# stepperDriverTop.net
KiCad netlist of a schematic drawn in EAGLE
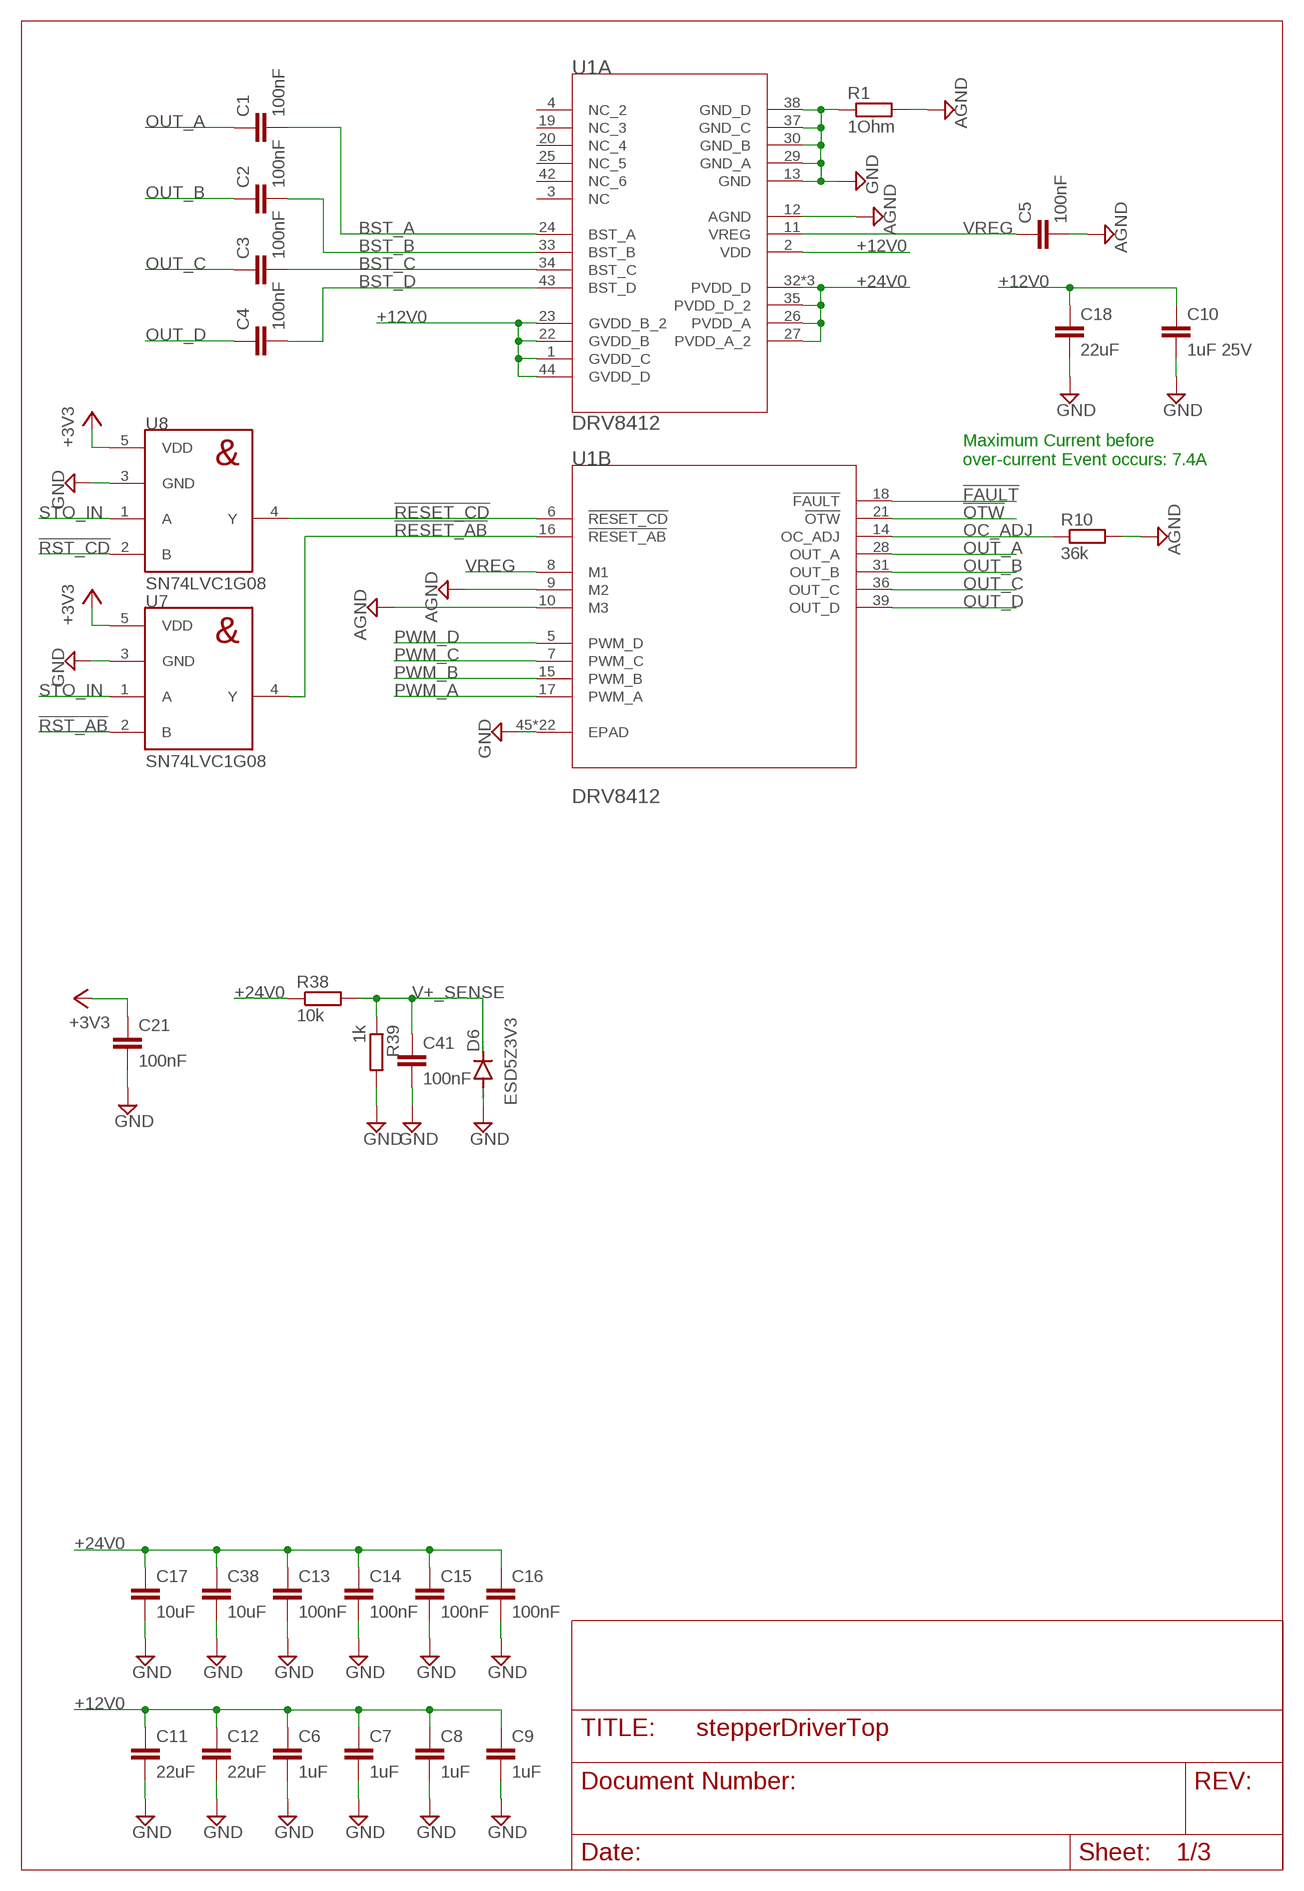
[diagram p0: schematic, sheet 1]
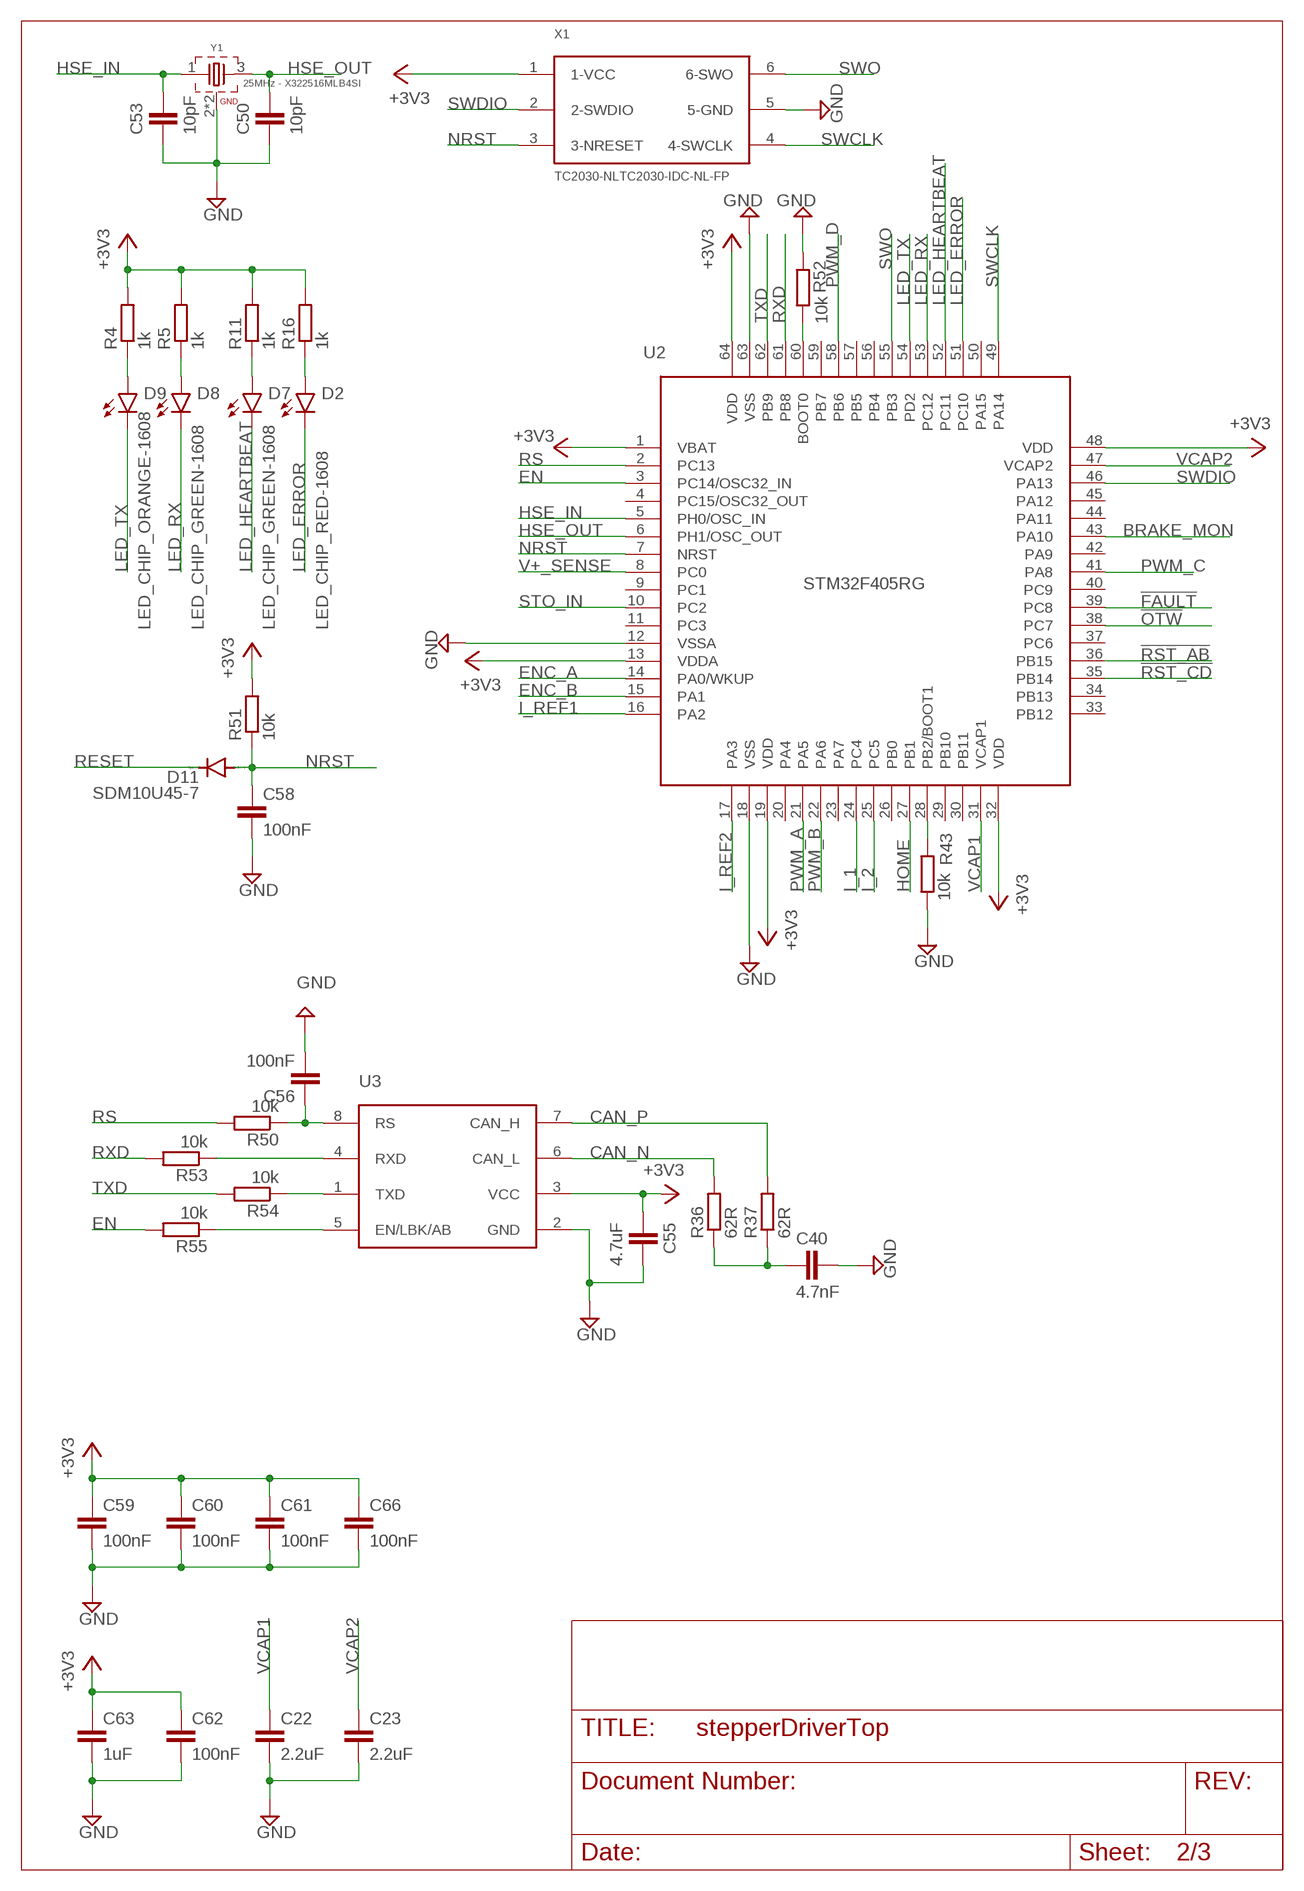
[diagram p1: schematic, sheet 2]
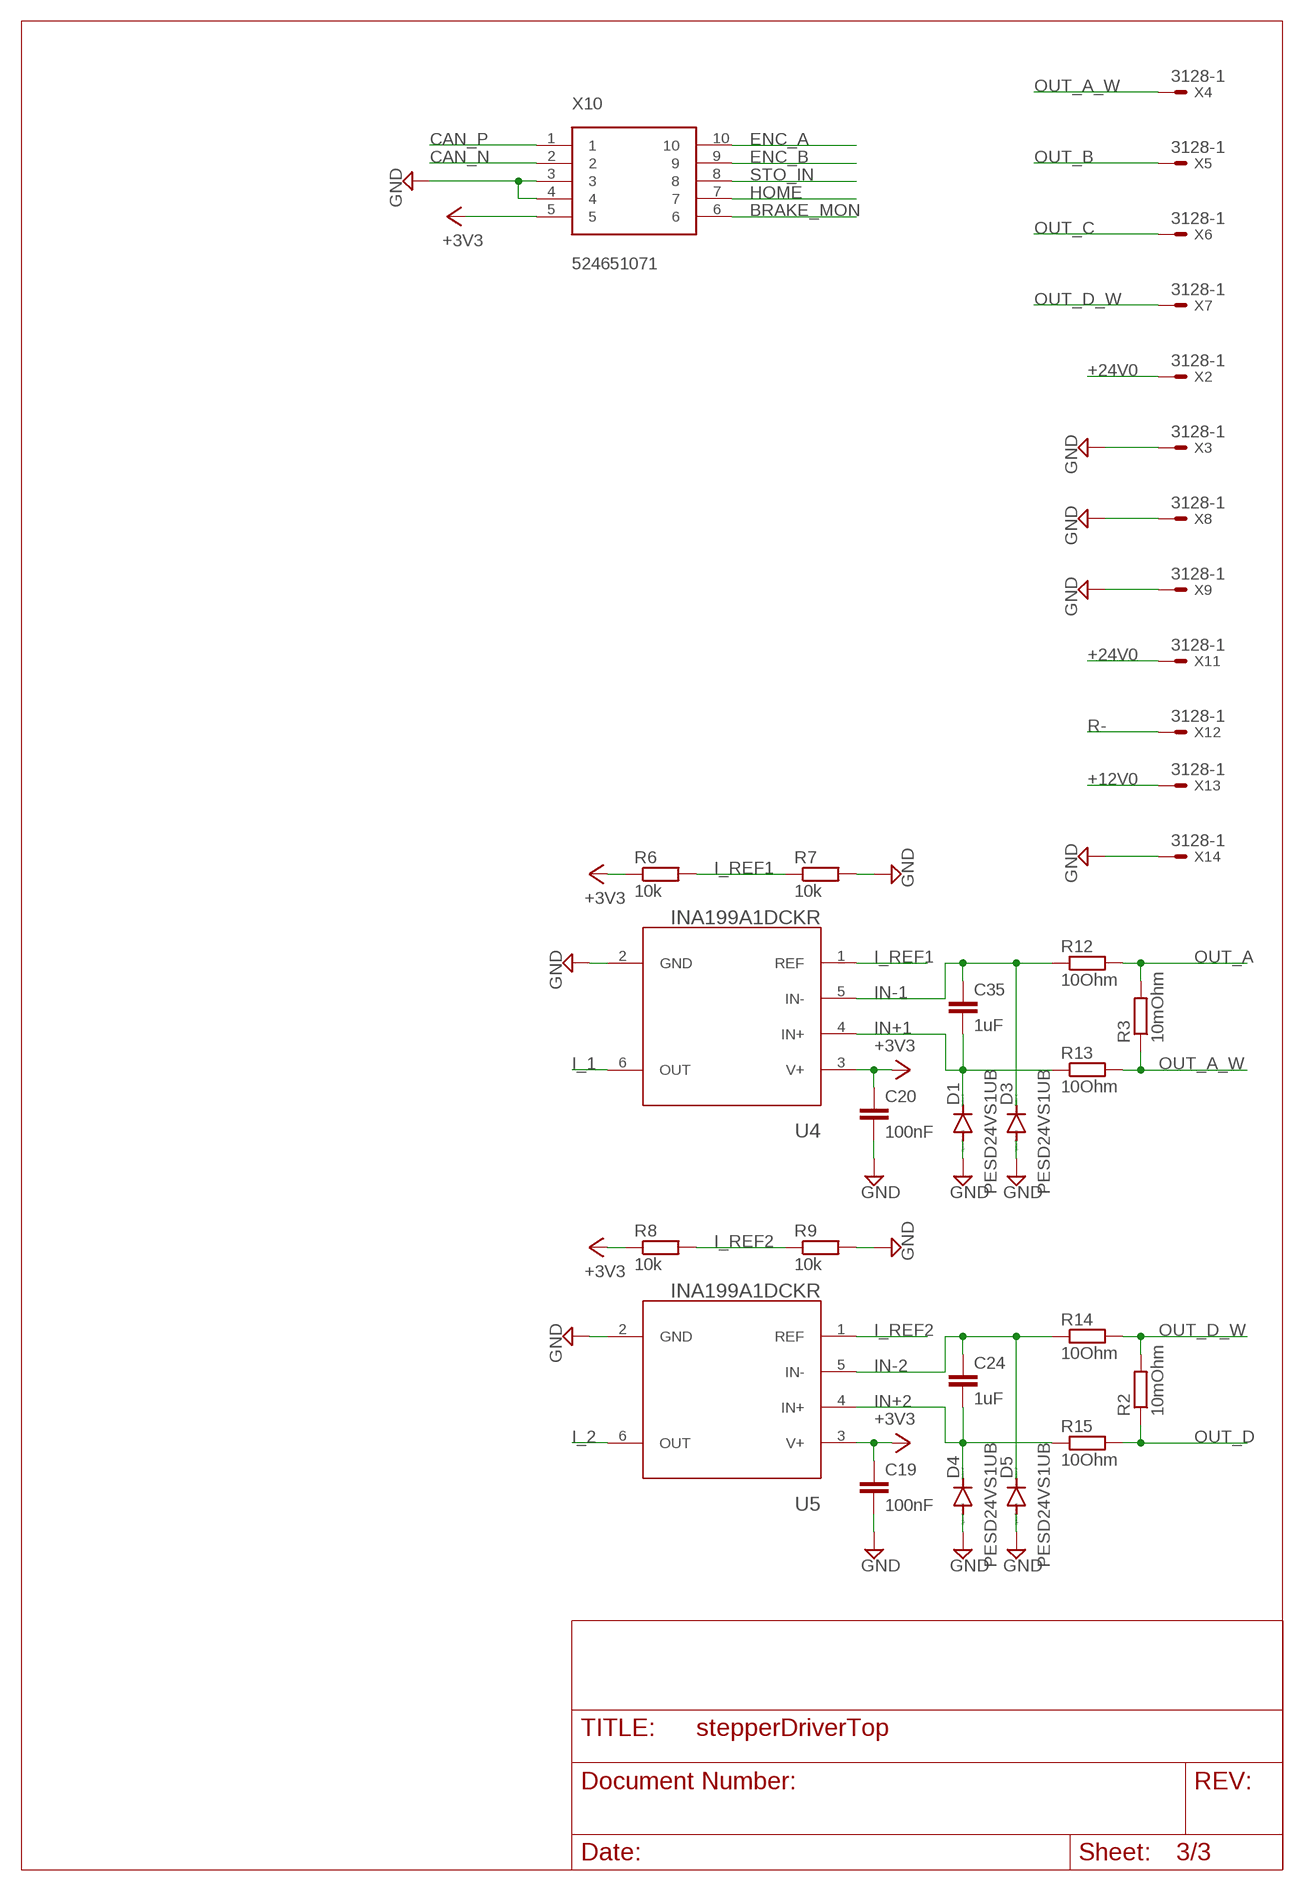
[diagram p2: schematic, sheet 3]

(export (version "E")
  (design (tool "Eeschema 10.0.6"))
  (components
    (comp (ref "C1")
      (value "100nF")
      (footprint "eagle-import:C0603")
      (libsource (lib "eagle-import") (part "C-EUC0603"))
    )
    (comp (ref "C2")
      (value "100nF")
      (footprint "eagle-import:C0603")
      (libsource (lib "eagle-import") (part "C-EUC0603"))
    )
    (comp (ref "C3")
      (value "100nF")
      (footprint "eagle-import:C0603")
      (libsource (lib "eagle-import") (part "C-EUC0603"))
    )
    (comp (ref "C4")
      (value "100nF")
      (footprint "eagle-import:C0603")
      (libsource (lib "eagle-import") (part "C-EUC0603"))
    )
    (comp (ref "C5")
      (value "100nF")
      (footprint "eagle-import:C0402")
      (libsource (lib "eagle-import") (part "C-EUC0402"))
    )
    (comp (ref "C6")
      (value "1uF")
      (footprint "eagle-import:C0402")
      (libsource (lib "eagle-import") (part "C-EUC0402"))
    )
    (comp (ref "C7")
      (value "1uF")
      (footprint "eagle-import:C0402")
      (libsource (lib "eagle-import") (part "C-EUC0402"))
    )
    (comp (ref "C8")
      (value "1uF")
      (footprint "eagle-import:C0402")
      (libsource (lib "eagle-import") (part "C-EUC0402"))
    )
    (comp (ref "C9")
      (value "1uF")
      (footprint "eagle-import:C0402")
      (libsource (lib "eagle-import") (part "C-EUC0402"))
    )
    (comp (ref "C10")
      (value "1uF 25V")
      (footprint "eagle-import:C0402")
      (libsource (lib "eagle-import") (part "C-EUC0402"))
    )
    (comp (ref "C11")
      (value "22uF")
      (footprint "eagle-import:C0805")
      (libsource (lib "eagle-import") (part "C-EUC0805"))
    )
    (comp (ref "C12")
      (value "22uF")
      (footprint "eagle-import:C0805")
      (libsource (lib "eagle-import") (part "C-EUC0805"))
    )
    (comp (ref "C13")
      (value "100nF")
      (footprint "eagle-import:C0402")
      (libsource (lib "eagle-import") (part "C-EUC0402"))
    )
    (comp (ref "C14")
      (value "100nF")
      (footprint "eagle-import:C0402")
      (libsource (lib "eagle-import") (part "C-EUC0402"))
    )
    (comp (ref "C15")
      (value "100nF")
      (footprint "eagle-import:C0402")
      (libsource (lib "eagle-import") (part "C-EUC0402"))
    )
    (comp (ref "C16")
      (value "100nF")
      (footprint "eagle-import:C0402")
      (libsource (lib "eagle-import") (part "C-EUC0402"))
    )
    (comp (ref "C17")
      (value "10uF")
      (footprint "eagle-import:C1206")
      (libsource (lib "eagle-import") (part "C-EUC1206"))
    )
    (comp (ref "C18")
      (value "22uF")
      (footprint "eagle-import:C0805")
      (libsource (lib "eagle-import") (part "C-EUC0805"))
    )
    (comp (ref "C21")
      (value "100nF")
      (footprint "eagle-import:C0402")
      (libsource (lib "eagle-import") (part "C-EUC0402"))
    )
    (comp (ref "C38")
      (value "10uF")
      (footprint "eagle-import:C1206")
      (libsource (lib "eagle-import") (part "C-EUC1206"))
    )
    (comp (ref "C41")
      (value "100nF")
      (footprint "eagle-import:C0402")
      (libsource (lib "eagle-import") (part "C-EUC0402"))
    )
    (comp (ref "D6")
      (value "ESD5Z3V3")
      (footprint "eagle-import:SOD523")
      (libsource (lib "eagle-import") (part "DIODE-SOD523"))
    )
    (comp (ref "R1")
      (value "1Ohm")
      (footprint "eagle-import:R0402")
      (libsource (lib "eagle-import") (part "R-EU_R0402"))
    )
    (comp (ref "R10")
      (value "36k")
      (footprint "eagle-import:R0402")
      (libsource (lib "eagle-import") (part "R-EU_R0402"))
    )
    (comp (ref "R38")
      (value "10k")
      (footprint "eagle-import:R0402")
      (libsource (lib "eagle-import") (part "R-EU_R0402"))
    )
    (comp (ref "R39")
      (value "1k")
      (footprint "eagle-import:R0402")
      (libsource (lib "eagle-import") (part "R-EU_R0402"))
    )
    (comp (ref "U1")
      (value "DRV8412")
      (footprint "eagle-import:SOP63P810X120-45T350X740N")
      (libsource (lib "eagle-import") (part "DRV8412DDW44"))
    )
    (comp (ref "U7")
      (value "SN74LVC1G08")
      (footprint "eagle-import:SOT95P240X110-5")
      (libsource (lib "eagle-import") (part "SN74LVC1G08"))
    )
    (comp (ref "U8")
      (value "SN74LVC1G08")
      (footprint "eagle-import:SOT95P240X110-5")
      (libsource (lib "eagle-import") (part "SN74LVC1G08"))
    )
    (comp (ref "C22")
      (value "2.2uF")
      (footprint "eagle-import:C0603")
      (libsource (lib "eagle-import") (part "C-EUC0603"))
    )
    (comp (ref "C23")
      (value "2.2uF")
      (footprint "eagle-import:C0603")
      (libsource (lib "eagle-import") (part "C-EUC0603"))
    )
    (comp (ref "C40")
      (value "4.7nF")
      (footprint "eagle-import:C0402")
      (libsource (lib "eagle-import") (part "C-EUC0402"))
    )
    (comp (ref "C50")
      (value "10pF")
      (footprint "eagle-import:C0402")
      (libsource (lib "eagle-import") (part "C-EUC0402"))
    )
    (comp (ref "C53")
      (value "10pF")
      (footprint "eagle-import:C0402")
      (libsource (lib "eagle-import") (part "C-EUC0402"))
    )
    (comp (ref "C55")
      (value "4.7uF")
      (footprint "eagle-import:C0402")
      (libsource (lib "eagle-import") (part "C-EUC0402"))
    )
    (comp (ref "C56")
      (value "100nF")
      (footprint "eagle-import:C0402")
      (libsource (lib "eagle-import") (part "C-EUC0402"))
    )
    (comp (ref "C58")
      (value "100nF")
      (footprint "eagle-import:C0402")
      (libsource (lib "eagle-import") (part "C-EUC0402"))
    )
    (comp (ref "C59")
      (value "100nF")
      (footprint "eagle-import:C0402")
      (libsource (lib "eagle-import") (part "C-EUC0402"))
    )
    (comp (ref "C60")
      (value "100nF")
      (footprint "eagle-import:C0402")
      (libsource (lib "eagle-import") (part "C-EUC0402"))
    )
    (comp (ref "C61")
      (value "100nF")
      (footprint "eagle-import:C0402")
      (libsource (lib "eagle-import") (part "C-EUC0402"))
    )
    (comp (ref "C62")
      (value "100nF")
      (footprint "eagle-import:C0402")
      (libsource (lib "eagle-import") (part "C-EUC0402"))
    )
    (comp (ref "C63")
      (value "1uF")
      (footprint "eagle-import:C0402")
      (libsource (lib "eagle-import") (part "C-EUC0402"))
    )
    (comp (ref "C66")
      (value "100nF")
      (footprint "eagle-import:C0402")
      (libsource (lib "eagle-import") (part "C-EUC0402"))
    )
    (comp (ref "D2")
      (value "LED_CHIP_RED-1608")
      (footprint "eagle-import:LEDC1608X39N_R")
      (libsource (lib "eagle-import") (part "LED_CHIPRED-1608_"))
    )
    (comp (ref "D7")
      (value "LED_CHIP_GREEN-1608")
      (footprint "eagle-import:LEDC1608X39N_G")
      (libsource (lib "eagle-import") (part "LED_CHIPGREEN-1608_"))
    )
    (comp (ref "D8")
      (value "LED_CHIP_GREEN-1608")
      (footprint "eagle-import:LEDC1608X39N_G")
      (libsource (lib "eagle-import") (part "LED_CHIPGREEN-1608_"))
    )
    (comp (ref "D9")
      (value "LED_CHIP_ORANGE-1608")
      (footprint "eagle-import:LEDC1608X39N_G")
      (libsource (lib "eagle-import") (part "LED_CHIPGREEN-1608_"))
    )
    (comp (ref "D11")
      (value "SDM10U45-7")
      (footprint "eagle-import:SOD523")
      (libsource (lib "eagle-import") (part "DIODE-SOD523"))
    )
    (comp (ref "R4")
      (value "1k")
      (footprint "eagle-import:R0402")
      (libsource (lib "eagle-import") (part "R-EU_R0402"))
    )
    (comp (ref "R5")
      (value "1k")
      (footprint "eagle-import:R0402")
      (libsource (lib "eagle-import") (part "R-EU_R0402"))
    )
    (comp (ref "R11")
      (value "1k")
      (footprint "eagle-import:R0402")
      (libsource (lib "eagle-import") (part "R-EU_R0402"))
    )
    (comp (ref "R16")
      (value "1k")
      (footprint "eagle-import:R0402")
      (libsource (lib "eagle-import") (part "R-EU_R0402"))
    )
    (comp (ref "R36")
      (value "62R")
      (footprint "eagle-import:R0603")
      (libsource (lib "eagle-import") (part "R-EU_R0603"))
    )
    (comp (ref "R37")
      (value "62R")
      (footprint "eagle-import:R0603")
      (libsource (lib "eagle-import") (part "R-EU_R0603"))
    )
    (comp (ref "R43")
      (value "10k")
      (footprint "eagle-import:R0402")
      (libsource (lib "eagle-import") (part "R-EU_R0402"))
    )
    (comp (ref "R50")
      (value "10k")
      (footprint "eagle-import:R0402")
      (libsource (lib "eagle-import") (part "R-EU_R0402"))
    )
    (comp (ref "R51")
      (value "10k")
      (footprint "eagle-import:R0402")
      (libsource (lib "eagle-import") (part "R-EU_R0402"))
    )
    (comp (ref "R52")
      (value "10k")
      (footprint "eagle-import:R0402")
      (libsource (lib "eagle-import") (part "R-EU_R0402"))
    )
    (comp (ref "R53")
      (value "10k")
      (footprint "eagle-import:R0402")
      (libsource (lib "eagle-import") (part "R-EU_R0402"))
    )
    (comp (ref "R54")
      (value "10k")
      (footprint "eagle-import:R0402")
      (libsource (lib "eagle-import") (part "R-EU_R0402"))
    )
    (comp (ref "R55")
      (value "10k")
      (footprint "eagle-import:R0402")
      (libsource (lib "eagle-import") (part "R-EU_R0402"))
    )
    (comp (ref "U2")
      (value "STM32F405RGLQFP64")
      (footprint "eagle-import:QFP50P1200X1200X120-64")
      (libsource (lib "eagle-import") (part "STM32F405RGLQFP64"))
    )
    (comp (ref "U3")
      (value "SN65HVD23X-Q1D0008A")
      (footprint "eagle-import:SOIC127P599X175-8N")
      (libsource (lib "eagle-import") (part "SN65HVD23X-Q1D0008A"))
    )
    (comp (ref "X1")
      (value "TC2030-NLTC2030-IDC-NL-FP")
      (footprint "eagle-import:TC2030-NL")
      (libsource (lib "eagle-import") (part "TC2030-NLTC2030-IDC-NL-FP"))
    )
    (comp (ref "Y1")
      (value "25MHz - X322516MLB4SI")
      (footprint "eagle-import:WE-XTAL_CFPX-180")
      (fields (field (name "TOLERANCE") "±10ppm"))
      (libsource (lib "eagle-import") (part "WE-XTAL_CFPX-180_830059800"))
    )
    (comp (ref "C19")
      (value "100nF")
      (footprint "eagle-import:C0402")
      (libsource (lib "eagle-import") (part "C-EUC0402"))
    )
    (comp (ref "C20")
      (value "100nF")
      (footprint "eagle-import:C0402")
      (libsource (lib "eagle-import") (part "C-EUC0402"))
    )
    (comp (ref "C24")
      (value "1uF")
      (footprint "eagle-import:C0402")
      (libsource (lib "eagle-import") (part "C-EUC0402"))
    )
    (comp (ref "C35")
      (value "1uF")
      (footprint "eagle-import:C0402")
      (libsource (lib "eagle-import") (part "C-EUC0402"))
    )
    (comp (ref "D1")
      (value "PESD24VS1UB")
      (footprint "eagle-import:SOD523")
      (libsource (lib "eagle-import") (part "DIODE-SOD523"))
    )
    (comp (ref "D3")
      (value "PESD24VS1UB")
      (footprint "eagle-import:SOD523")
      (libsource (lib "eagle-import") (part "DIODE-SOD523"))
    )
    (comp (ref "D4")
      (value "PESD24VS1UB")
      (footprint "eagle-import:SOD523")
      (libsource (lib "eagle-import") (part "DIODE-SOD523"))
    )
    (comp (ref "D5")
      (value "PESD24VS1UB")
      (footprint "eagle-import:SOD523")
      (libsource (lib "eagle-import") (part "DIODE-SOD523"))
    )
    (comp (ref "R2")
      (value "10mOhm")
      (footprint "eagle-import:R0805")
      (libsource (lib "eagle-import") (part "R-EU_R0805"))
    )
    (comp (ref "R3")
      (value "10mOhm")
      (footprint "eagle-import:R0805")
      (libsource (lib "eagle-import") (part "R-EU_R0805"))
    )
    (comp (ref "R6")
      (value "10k")
      (footprint "eagle-import:R0402")
      (libsource (lib "eagle-import") (part "R-EU_R0402"))
    )
    (comp (ref "R7")
      (value "10k")
      (footprint "eagle-import:R0402")
      (libsource (lib "eagle-import") (part "R-EU_R0402"))
    )
    (comp (ref "R8")
      (value "10k")
      (footprint "eagle-import:R0402")
      (libsource (lib "eagle-import") (part "R-EU_R0402"))
    )
    (comp (ref "R9")
      (value "10k")
      (footprint "eagle-import:R0402")
      (libsource (lib "eagle-import") (part "R-EU_R0402"))
    )
    (comp (ref "R12")
      (value "10Ohm")
      (footprint "eagle-import:R0402")
      (libsource (lib "eagle-import") (part "R-EU_R0402"))
    )
    (comp (ref "R13")
      (value "10Ohm")
      (footprint "eagle-import:R0402")
      (libsource (lib "eagle-import") (part "R-EU_R0402"))
    )
    (comp (ref "R14")
      (value "10Ohm")
      (footprint "eagle-import:R0402")
      (libsource (lib "eagle-import") (part "R-EU_R0402"))
    )
    (comp (ref "R15")
      (value "10Ohm")
      (footprint "eagle-import:R0402")
      (libsource (lib "eagle-import") (part "R-EU_R0402"))
    )
    (comp (ref "U4")
      (value "INA199A1DCKR")
      (footprint "eagle-import:SOP65P210X110-6N")
      (libsource (lib "eagle-import") (part "INA199SC70"))
    )
    (comp (ref "U5")
      (value "INA199A1DCKR")
      (footprint "eagle-import:SOP65P210X110-6N")
      (libsource (lib "eagle-import") (part "INA199SC70"))
    )
    (comp (ref "X2")
      (value "3128-1")
      (footprint "eagle-import:3128-1")
      (libsource (lib "eagle-import") (part "3128-10.6MM"))
    )
    (comp (ref "X3")
      (value "3128-1")
      (footprint "eagle-import:3128-1")
      (libsource (lib "eagle-import") (part "3128-10.6MM"))
    )
    (comp (ref "X4")
      (value "3128-1")
      (footprint "eagle-import:3128-1")
      (libsource (lib "eagle-import") (part "3128-10.6MM"))
    )
    (comp (ref "X5")
      (value "3128-1")
      (footprint "eagle-import:3128-1")
      (libsource (lib "eagle-import") (part "3128-10.6MM"))
    )
    (comp (ref "X6")
      (value "3128-1")
      (footprint "eagle-import:3128-1")
      (libsource (lib "eagle-import") (part "3128-10.6MM"))
    )
    (comp (ref "X7")
      (value "3128-1")
      (footprint "eagle-import:3128-1")
      (libsource (lib "eagle-import") (part "3128-10.6MM"))
    )
    (comp (ref "X8")
      (value "3128-1")
      (footprint "eagle-import:3128-1")
      (libsource (lib "eagle-import") (part "3128-10.6MM"))
    )
    (comp (ref "X9")
      (value "3128-1")
      (footprint "eagle-import:3128-1")
      (libsource (lib "eagle-import") (part "3128-10.6MM"))
    )
    (comp (ref "X10")
      (value "524651071")
      (footprint "eagle-import:524651071")
      (libsource (lib "eagle-import") (part "524651071SMD"))
    )
    (comp (ref "X11")
      (value "3128-1")
      (footprint "eagle-import:3128-1")
      (libsource (lib "eagle-import") (part "3128-10.6MM"))
    )
    (comp (ref "X12")
      (value "3128-1")
      (footprint "eagle-import:3128-1")
      (libsource (lib "eagle-import") (part "3128-10.6MM"))
    )
    (comp (ref "X13")
      (value "3128-1")
      (footprint "eagle-import:3128-1")
      (libsource (lib "eagle-import") (part "3128-10.6MM"))
    )
    (comp (ref "X14")
      (value "3128-1")
      (footprint "eagle-import:3128-1")
      (libsource (lib "eagle-import") (part "3128-10.6MM"))
    )
  )
  (nets
    (net (code "1") (name "+3V3") (class "Default")
      (node (ref "C19") (pin "1") (pinfunction "1_1") (pintype "passive"))
      (node (ref "C20") (pin "1") (pinfunction "1_1") (pintype "passive"))
      (node (ref "C21") (pin "1") (pinfunction "1_1") (pintype "passive"))
      (node (ref "C55") (pin "2") (pinfunction "2_2") (pintype "passive"))
      (node (ref "C59") (pin "1") (pinfunction "1_1") (pintype "passive"))
      (node (ref "C60") (pin "1") (pinfunction "1_1") (pintype "passive"))
      (node (ref "C61") (pin "1") (pinfunction "1_1") (pintype "passive"))
      (node (ref "C62") (pin "1") (pinfunction "1_1") (pintype "passive"))
      (node (ref "C63") (pin "1") (pinfunction "1_1") (pintype "passive"))
      (node (ref "C66") (pin "1") (pinfunction "1_1") (pintype "passive"))
      (node (ref "R11") (pin "2") (pinfunction "2_2") (pintype "passive"))
      (node (ref "R16") (pin "2") (pinfunction "2_2") (pintype "passive"))
      (node (ref "R4") (pin "2") (pinfunction "2_2") (pintype "passive"))
      (node (ref "R5") (pin "2") (pinfunction "2_2") (pintype "passive"))
      (node (ref "R51") (pin "2") (pinfunction "2_2") (pintype "passive"))
      (node (ref "R6") (pin "1") (pinfunction "1_1") (pintype "passive"))
      (node (ref "R8") (pin "1") (pinfunction "1_1") (pintype "passive"))
      (node (ref "U2") (pin "1") (pinfunction "VBAT_1") (pintype "bidirectional"))
      (node (ref "U2") (pin "13") (pinfunction "VDDA_13") (pintype "bidirectional"))
      (node (ref "U2") (pin "19") (pinfunction "VDD_19") (pintype "bidirectional"))
      (node (ref "U2") (pin "32") (pinfunction "VDD_32") (pintype "bidirectional"))
      (node (ref "U2") (pin "48") (pinfunction "VDD_48") (pintype "bidirectional"))
      (node (ref "U2") (pin "64") (pinfunction "VDD_64") (pintype "bidirectional"))
      (node (ref "U3") (pin "3") (pinfunction "VCC_3") (pintype "bidirectional"))
      (node (ref "U4") (pin "3") (pinfunction "V+_3") (pintype "power_in"))
      (node (ref "U5") (pin "3") (pinfunction "V+_3") (pintype "power_in"))
      (node (ref "U7") (pin "5") (pinfunction "VDD_5") (pintype "bidirectional"))
      (node (ref "U8") (pin "5") (pinfunction "VDD_5") (pintype "bidirectional"))
      (node (ref "X1") (pin "1") (pinfunction "1-VCC_1") (pintype "bidirectional"))
      (node (ref "X10") (pin "5") (pinfunction "5_5") (pintype "bidirectional"))
    )
    (net (code "2") (name "+12V0") (class "Default")
      (node (ref "C10") (pin "1") (pinfunction "1_1") (pintype "passive"))
      (node (ref "C11") (pin "1") (pinfunction "1_1") (pintype "passive"))
      (node (ref "C12") (pin "1") (pinfunction "1_1") (pintype "passive"))
      (node (ref "C18") (pin "1") (pinfunction "1_1") (pintype "passive"))
      (node (ref "C6") (pin "1") (pinfunction "1_1") (pintype "passive"))
      (node (ref "C7") (pin "1") (pinfunction "1_1") (pintype "passive"))
      (node (ref "C8") (pin "1") (pinfunction "1_1") (pintype "passive"))
      (node (ref "C9") (pin "1") (pinfunction "1_1") (pintype "passive"))
      (node (ref "U1") (pin "1") (pinfunction "GVDD_C_1") (pintype "passive"))
      (node (ref "U1") (pin "2") (pinfunction "VDD_2") (pintype "passive"))
      (node (ref "U1") (pin "22") (pinfunction "GVDD_B_22") (pintype "passive"))
      (node (ref "U1") (pin "23") (pinfunction "GVDD_B_2_23") (pintype "passive"))
      (node (ref "U1") (pin "44") (pinfunction "GVDD_D_44") (pintype "passive"))
      (node (ref "X13") (pin "PIN1") (pinfunction "S_PIN1") (pintype "passive"))
    )
    (net (code "3") (name "+24V0") (class "Default")
      (node (ref "C13") (pin "1") (pinfunction "1_1") (pintype "passive"))
      (node (ref "C14") (pin "1") (pinfunction "1_1") (pintype "passive"))
      (node (ref "C15") (pin "1") (pinfunction "1_1") (pintype "passive"))
      (node (ref "C16") (pin "1") (pinfunction "1_1") (pintype "passive"))
      (node (ref "C17") (pin "1") (pinfunction "1_1") (pintype "passive"))
      (node (ref "C38") (pin "1") (pinfunction "1_1") (pintype "passive"))
      (node (ref "R38") (pin "1") (pinfunction "1_1") (pintype "passive"))
      (node (ref "U1") (pin "26") (pinfunction "PVDD_A_26") (pintype "passive"))
      (node (ref "U1") (pin "27") (pinfunction "PVDD_A_2_27") (pintype "passive"))
      (node (ref "U1") (pin "32") (pinfunction "PVDD_D_32") (pintype "passive"))
      (node (ref "U1") (pin "35") (pinfunction "PVDD_D_2_35") (pintype "passive"))
      (node (ref "U1") (pin "40") (pinfunction "PVDD_D_40") (pintype "passive"))
      (node (ref "U1") (pin "41") (pinfunction "PVDD_D_41") (pintype "passive"))
      (node (ref "X11") (pin "PIN1") (pinfunction "S_PIN1") (pintype "passive"))
      (node (ref "X2") (pin "PIN1") (pinfunction "S_PIN1") (pintype "passive"))
    )
    (net (code "4") (name "AGND") (class "Default")
      (node (ref "C5") (pin "2") (pinfunction "2_2") (pintype "passive"))
      (node (ref "R1") (pin "2") (pinfunction "2_2") (pintype "passive"))
      (node (ref "R10") (pin "2") (pinfunction "2_2") (pintype "passive"))
      (node (ref "U1") (pin "10") (pinfunction "M3_10") (pintype "passive"))
      (node (ref "U1") (pin "12") (pinfunction "AGND_12") (pintype "passive"))
      (node (ref "U1") (pin "9") (pinfunction "M2_9") (pintype "passive"))
    )
    (net (code "5") (name "BRAKE_MON") (class "Default")
      (node (ref "U2") (pin "43") (pinfunction "PA10_43") (pintype "bidirectional"))
      (node (ref "X10") (pin "6") (pinfunction "6_6") (pintype "bidirectional"))
    )
    (net (code "6") (name "BST_A") (class "Default")
      (node (ref "C1") (pin "2") (pinfunction "2_2") (pintype "passive"))
      (node (ref "U1") (pin "24") (pinfunction "BST_A_24") (pintype "passive"))
    )
    (net (code "7") (name "BST_B") (class "Default")
      (node (ref "C2") (pin "2") (pinfunction "2_2") (pintype "passive"))
      (node (ref "U1") (pin "33") (pinfunction "BST_B_33") (pintype "passive"))
    )
    (net (code "8") (name "BST_C") (class "Default")
      (node (ref "C3") (pin "2") (pinfunction "2_2") (pintype "passive"))
      (node (ref "U1") (pin "34") (pinfunction "BST_C_34") (pintype "passive"))
    )
    (net (code "9") (name "BST_D") (class "Default")
      (node (ref "C4") (pin "2") (pinfunction "2_2") (pintype "passive"))
      (node (ref "U1") (pin "43") (pinfunction "BST_D_43") (pintype "passive"))
    )
    (net (code "10") (name "CAN_N") (class "Default")
      (node (ref "R36") (pin "2") (pinfunction "2_2") (pintype "passive"))
      (node (ref "U3") (pin "6") (pinfunction "CAN_L_6") (pintype "bidirectional"))
      (node (ref "X10") (pin "2") (pinfunction "2_2") (pintype "bidirectional"))
    )
    (net (code "11") (name "CAN_P") (class "Default")
      (node (ref "R37") (pin "2") (pinfunction "2_2") (pintype "passive"))
      (node (ref "U3") (pin "7") (pinfunction "CAN_H_7") (pintype "bidirectional"))
      (node (ref "X10") (pin "1") (pinfunction "1_1") (pintype "bidirectional"))
    )
    (net (code "12") (name "EN") (class "Default")
      (node (ref "R55") (pin "2") (pinfunction "2_2") (pintype "passive"))
      (node (ref "U2") (pin "3") (pinfunction "PC14/OSC32_IN_3") (pintype "bidirectional"))
    )
    (net (code "13") (name "ENC_A") (class "Default")
      (node (ref "U2") (pin "14") (pinfunction "PA0/WKUP_14") (pintype "bidirectional"))
      (node (ref "X10") (pin "10") (pinfunction "10_10") (pintype "bidirectional"))
    )
    (net (code "14") (name "ENC_B") (class "Default")
      (node (ref "U2") (pin "15") (pinfunction "PA1_15") (pintype "bidirectional"))
      (node (ref "X10") (pin "9") (pinfunction "9_9") (pintype "bidirectional"))
    )
    (net (code "15") (name "GND") (class "Default")
      (node (ref "C10") (pin "2") (pinfunction "2_2") (pintype "passive"))
      (node (ref "C11") (pin "2") (pinfunction "2_2") (pintype "passive"))
      (node (ref "C12") (pin "2") (pinfunction "2_2") (pintype "passive"))
      (node (ref "C13") (pin "2") (pinfunction "2_2") (pintype "passive"))
      (node (ref "C14") (pin "2") (pinfunction "2_2") (pintype "passive"))
      (node (ref "C15") (pin "2") (pinfunction "2_2") (pintype "passive"))
      (node (ref "C16") (pin "2") (pinfunction "2_2") (pintype "passive"))
      (node (ref "C17") (pin "2") (pinfunction "2_2") (pintype "passive"))
      (node (ref "C18") (pin "2") (pinfunction "2_2") (pintype "passive"))
      (node (ref "C19") (pin "2") (pinfunction "2_2") (pintype "passive"))
      (node (ref "C20") (pin "2") (pinfunction "2_2") (pintype "passive"))
      (node (ref "C21") (pin "2") (pinfunction "2_2") (pintype "passive"))
      (node (ref "C22") (pin "2") (pinfunction "2_2") (pintype "passive"))
      (node (ref "C23") (pin "2") (pinfunction "2_2") (pintype "passive"))
      (node (ref "C38") (pin "2") (pinfunction "2_2") (pintype "passive"))
      (node (ref "C40") (pin "1") (pinfunction "1_1") (pintype "passive"))
      (node (ref "C41") (pin "2") (pinfunction "2_2") (pintype "passive"))
      (node (ref "C50") (pin "2") (pinfunction "2_2") (pintype "passive"))
      (node (ref "C53") (pin "2") (pinfunction "2_2") (pintype "passive"))
      (node (ref "C55") (pin "1") (pinfunction "1_1") (pintype "passive"))
      (node (ref "C56") (pin "2") (pinfunction "2_2") (pintype "passive"))
      (node (ref "C58") (pin "2") (pinfunction "2_2") (pintype "passive"))
      (node (ref "C59") (pin "2") (pinfunction "2_2") (pintype "passive"))
      (node (ref "C6") (pin "2") (pinfunction "2_2") (pintype "passive"))
      (node (ref "C60") (pin "2") (pinfunction "2_2") (pintype "passive"))
      (node (ref "C61") (pin "2") (pinfunction "2_2") (pintype "passive"))
      (node (ref "C62") (pin "2") (pinfunction "2_2") (pintype "passive"))
      (node (ref "C63") (pin "2") (pinfunction "2_2") (pintype "passive"))
      (node (ref "C66") (pin "2") (pinfunction "2_2") (pintype "passive"))
      (node (ref "C7") (pin "2") (pinfunction "2_2") (pintype "passive"))
      (node (ref "C8") (pin "2") (pinfunction "2_2") (pintype "passive"))
      (node (ref "C9") (pin "2") (pinfunction "2_2") (pintype "passive"))
      (node (ref "D1") (pin "A") (pinfunction "A_A") (pintype "passive"))
      (node (ref "D3") (pin "A") (pinfunction "A_A") (pintype "passive"))
      (node (ref "D4") (pin "A") (pinfunction "A_A") (pintype "passive"))
      (node (ref "D5") (pin "A") (pinfunction "A_A") (pintype "passive"))
      (node (ref "D6") (pin "A") (pinfunction "A_A") (pintype "passive"))
      (node (ref "R1") (pin "1") (pinfunction "1_1") (pintype "passive"))
      (node (ref "R39") (pin "2") (pinfunction "2_2") (pintype "passive"))
      (node (ref "R43") (pin "1") (pinfunction "1_1") (pintype "passive"))
      (node (ref "R52") (pin "1") (pinfunction "1_1") (pintype "passive"))
      (node (ref "R7") (pin "2") (pinfunction "2_2") (pintype "passive"))
      (node (ref "R9") (pin "2") (pinfunction "2_2") (pintype "passive"))
      (node (ref "U1") (pin "13") (pinfunction "GND_13") (pintype "passive"))
      (node (ref "U1") (pin "29") (pinfunction "GND_A_29") (pintype "passive"))
      (node (ref "U1") (pin "30") (pinfunction "GND_B_30") (pintype "passive"))
      (node (ref "U1") (pin "37") (pinfunction "GND_C_37") (pintype "passive"))
      (node (ref "U1") (pin "38") (pinfunction "GND_D_38") (pintype "passive"))
      (node (ref "U1") (pin "45") (pinfunction "EPAD_45") (pintype "passive"))
      (node (ref "U1") (pin "V_1") (pinfunction "EPAD_V_1") (pintype "passive"))
      (node (ref "U1") (pin "V_10") (pinfunction "EPAD_V_10") (pintype "passive"))
      (node (ref "U1") (pin "V_11") (pinfunction "EPAD_V_11") (pintype "passive"))
      (node (ref "U1") (pin "V_12") (pinfunction "EPAD_V_12") (pintype "passive"))
      (node (ref "U1") (pin "V_13") (pinfunction "EPAD_V_13") (pintype "passive"))
      (node (ref "U1") (pin "V_14") (pinfunction "EPAD_V_14") (pintype "passive"))
      (node (ref "U1") (pin "V_15") (pinfunction "EPAD_V_15") (pintype "passive"))
      (node (ref "U1") (pin "V_16") (pinfunction "EPAD_V_16") (pintype "passive"))
      (node (ref "U1") (pin "V_17") (pinfunction "EPAD_V_17") (pintype "passive"))
      (node (ref "U1") (pin "V_18") (pinfunction "EPAD_V_18") (pintype "passive"))
      (node (ref "U1") (pin "V_19") (pinfunction "EPAD_V_19") (pintype "passive"))
      (node (ref "U1") (pin "V_2") (pinfunction "EPAD_V_2") (pintype "passive"))
      (node (ref "U1") (pin "V_20") (pinfunction "EPAD_V_20") (pintype "passive"))
      (node (ref "U1") (pin "V_21") (pinfunction "EPAD_V_21") (pintype "passive"))
      (node (ref "U1") (pin "V_3") (pinfunction "EPAD_V_3") (pintype "passive"))
      (node (ref "U1") (pin "V_4") (pinfunction "EPAD_V_4") (pintype "passive"))
      (node (ref "U1") (pin "V_5") (pinfunction "EPAD_V_5") (pintype "passive"))
      (node (ref "U1") (pin "V_6") (pinfunction "EPAD_V_6") (pintype "passive"))
      (node (ref "U1") (pin "V_7") (pinfunction "EPAD_V_7") (pintype "passive"))
      (node (ref "U1") (pin "V_8") (pinfunction "EPAD_V_8") (pintype "passive"))
      (node (ref "U1") (pin "V_9") (pinfunction "EPAD_V_9") (pintype "passive"))
      (node (ref "U2") (pin "12") (pinfunction "VSSA_12") (pintype "bidirectional"))
      (node (ref "U2") (pin "18") (pinfunction "VSS_18") (pintype "bidirectional"))
      (node (ref "U2") (pin "63") (pinfunction "VSS_63") (pintype "bidirectional"))
      (node (ref "U3") (pin "2") (pinfunction "GND_2") (pintype "bidirectional"))
      (node (ref "U4") (pin "2") (pinfunction "GND_2") (pintype "power_in"))
      (node (ref "U5") (pin "2") (pinfunction "GND_2") (pintype "power_in"))
      (node (ref "U7") (pin "3") (pinfunction "GND_3") (pintype "bidirectional"))
      (node (ref "U8") (pin "3") (pinfunction "GND_3") (pintype "bidirectional"))
      (node (ref "X1") (pin "5") (pinfunction "5-GND_5") (pintype "bidirectional"))
      (node (ref "X10") (pin "3") (pinfunction "3_3") (pintype "bidirectional"))
      (node (ref "X10") (pin "4") (pinfunction "4_4") (pintype "bidirectional"))
      (node (ref "X14") (pin "PIN1") (pinfunction "S_PIN1") (pintype "passive"))
      (node (ref "X3") (pin "PIN1") (pinfunction "S_PIN1") (pintype "passive"))
      (node (ref "X8") (pin "PIN1") (pinfunction "S_PIN1") (pintype "passive"))
      (node (ref "X9") (pin "PIN1") (pinfunction "S_PIN1") (pintype "passive"))
      (node (ref "Y1") (pin "2") (pinfunction "GND_2") (pintype "passive"))
      (node (ref "Y1") (pin "4") (pinfunction "GND_4") (pintype "passive"))
    )
    (net (code "16") (name "HOME") (class "Default")
      (node (ref "U2") (pin "27") (pinfunction "PB1_27") (pintype "bidirectional"))
      (node (ref "X10") (pin "7") (pinfunction "7_7") (pintype "bidirectional"))
    )
    (net (code "17") (name "HSE_IN") (class "Default")
      (node (ref "C53") (pin "1") (pinfunction "1_1") (pintype "passive"))
      (node (ref "U2") (pin "5") (pinfunction "PH0/OSC_IN_5") (pintype "bidirectional"))
      (node (ref "Y1") (pin "1") (pinfunction "1_1") (pintype "passive"))
    )
    (net (code "18") (name "HSE_OUT") (class "Default")
      (node (ref "C50") (pin "1") (pinfunction "1_1") (pintype "passive"))
      (node (ref "U2") (pin "6") (pinfunction "PH1/OSC_OUT_6") (pintype "bidirectional"))
      (node (ref "Y1") (pin "3") (pinfunction "2_3") (pintype "passive"))
    )
    (net (code "19") (name "IN+1") (class "Default")
      (node (ref "C35") (pin "2") (pinfunction "2_2") (pintype "passive"))
      (node (ref "D1") (pin "C") (pinfunction "C_C") (pintype "passive"))
      (node (ref "R13") (pin "1") (pinfunction "1_1") (pintype "passive"))
      (node (ref "U4") (pin "4") (pinfunction "IN+_4") (pintype "input"))
    )
    (net (code "20") (name "IN+2") (class "Default")
      (node (ref "C24") (pin "2") (pinfunction "2_2") (pintype "passive"))
      (node (ref "D4") (pin "C") (pinfunction "C_C") (pintype "passive"))
      (node (ref "R15") (pin "1") (pinfunction "1_1") (pintype "passive"))
      (node (ref "U5") (pin "4") (pinfunction "IN+_4") (pintype "input"))
    )
    (net (code "21") (name "IN-1") (class "Default")
      (node (ref "C35") (pin "1") (pinfunction "1_1") (pintype "passive"))
      (node (ref "D3") (pin "C") (pinfunction "C_C") (pintype "passive"))
      (node (ref "R12") (pin "1") (pinfunction "1_1") (pintype "passive"))
      (node (ref "U4") (pin "5") (pinfunction "IN-_5") (pintype "input"))
    )
    (net (code "22") (name "IN-2") (class "Default")
      (node (ref "C24") (pin "1") (pinfunction "1_1") (pintype "passive"))
      (node (ref "D5") (pin "C") (pinfunction "C_C") (pintype "passive"))
      (node (ref "R14") (pin "1") (pinfunction "1_1") (pintype "passive"))
      (node (ref "U5") (pin "5") (pinfunction "IN-_5") (pintype "input"))
    )
    (net (code "23") (name "I_1") (class "Default")
      (node (ref "U2") (pin "24") (pinfunction "PC4_24") (pintype "bidirectional"))
      (node (ref "U4") (pin "6") (pinfunction "OUT_6") (pintype "output"))
    )
    (net (code "24") (name "I_2") (class "Default")
      (node (ref "U2") (pin "25") (pinfunction "PC5_25") (pintype "bidirectional"))
      (node (ref "U5") (pin "6") (pinfunction "OUT_6") (pintype "output"))
    )
    (net (code "25") (name "I_REF1") (class "Default")
      (node (ref "R6") (pin "2") (pinfunction "2_2") (pintype "passive"))
      (node (ref "R7") (pin "1") (pinfunction "1_1") (pintype "passive"))
      (node (ref "U2") (pin "16") (pinfunction "PA2_16") (pintype "bidirectional"))
      (node (ref "U4") (pin "1") (pinfunction "REF_1") (pintype "input"))
    )
    (net (code "26") (name "I_REF2") (class "Default")
      (node (ref "R8") (pin "2") (pinfunction "2_2") (pintype "passive"))
      (node (ref "R9") (pin "1") (pinfunction "1_1") (pintype "passive"))
      (node (ref "U2") (pin "17") (pinfunction "PA3_17") (pintype "bidirectional"))
      (node (ref "U5") (pin "1") (pinfunction "REF_1") (pintype "input"))
    )
    (net (code "27") (name "LED_ERROR") (class "Default")
      (node (ref "D2") (pin "1") (pinfunction "C_1") (pintype "passive"))
      (node (ref "U2") (pin "51") (pinfunction "PC10_51") (pintype "bidirectional"))
    )
    (net (code "28") (name "LED_HEARTBEAT") (class "Default")
      (node (ref "D7") (pin "1") (pinfunction "C_1") (pintype "passive"))
      (node (ref "U2") (pin "52") (pinfunction "PC11_52") (pintype "bidirectional"))
    )
    (net (code "29") (name "LED_RX") (class "Default")
      (node (ref "D8") (pin "1") (pinfunction "C_1") (pintype "passive"))
      (node (ref "U2") (pin "53") (pinfunction "PC12_53") (pintype "bidirectional"))
    )
    (net (code "30") (name "LED_TX") (class "Default")
      (node (ref "D9") (pin "1") (pinfunction "C_1") (pintype "passive"))
      (node (ref "U2") (pin "54") (pinfunction "PD2_54") (pintype "bidirectional"))
    )
    (net (code "31") (name "NRST") (class "Default")
      (node (ref "C58") (pin "1") (pinfunction "1_1") (pintype "passive"))
      (node (ref "D11") (pin "A") (pinfunction "A_A") (pintype "passive"))
      (node (ref "R51") (pin "1") (pinfunction "1_1") (pintype "passive"))
      (node (ref "U2") (pin "7") (pinfunction "NRST_7") (pintype "bidirectional"))
      (node (ref "X1") (pin "3") (pinfunction "3-NRESET_3") (pintype "bidirectional"))
    )
    (net (code "32") (name "Net-(C40-Pad2)") (class "Default")
      (node (ref "C40") (pin "2") (pinfunction "2_2") (pintype "passive"))
      (node (ref "R36") (pin "1") (pinfunction "1_1") (pintype "passive"))
      (node (ref "R37") (pin "1") (pinfunction "1_1") (pintype "passive"))
    )
    (net (code "33") (name "Net-(D2-A)") (class "Default")
      (node (ref "D2") (pin "2") (pinfunction "A_2") (pintype "passive"))
      (node (ref "R16") (pin "1") (pinfunction "1_1") (pintype "passive"))
    )
    (net (code "34") (name "Net-(D7-A)") (class "Default")
      (node (ref "D7") (pin "2") (pinfunction "A_2") (pintype "passive"))
      (node (ref "R11") (pin "1") (pinfunction "1_1") (pintype "passive"))
    )
    (net (code "35") (name "Net-(D8-A)") (class "Default")
      (node (ref "D8") (pin "2") (pinfunction "A_2") (pintype "passive"))
      (node (ref "R5") (pin "1") (pinfunction "1_1") (pintype "passive"))
    )
    (net (code "36") (name "Net-(D9-A)") (class "Default")
      (node (ref "D9") (pin "2") (pinfunction "A_2") (pintype "passive"))
      (node (ref "R4") (pin "1") (pinfunction "1_1") (pintype "passive"))
    )
    (net (code "37") (name "Net-(U2-BOOT0)") (class "Default")
      (node (ref "R52") (pin "2") (pinfunction "2_2") (pintype "passive"))
      (node (ref "U2") (pin "60") (pinfunction "BOOT0_60") (pintype "bidirectional"))
    )
    (net (code "38") (name "Net-(U2-PB2{slash}BOOT1)") (class "Default")
      (node (ref "R43") (pin "2") (pinfunction "2_2") (pintype "passive"))
      (node (ref "U2") (pin "28") (pinfunction "PB2/BOOT1_28") (pintype "bidirectional"))
    )
    (net (code "39") (name "Net-(U3-EN{slash}LBK{slash}AB)") (class "Default")
      (node (ref "R55") (pin "1") (pinfunction "1_1") (pintype "passive"))
      (node (ref "U3") (pin "5") (pinfunction "EN/LBK/AB_5") (pintype "bidirectional"))
    )
    (net (code "40") (name "Net-(U3-RS)") (class "Default")
      (node (ref "C56") (pin "1") (pinfunction "1_1") (pintype "passive"))
      (node (ref "R50") (pin "1") (pinfunction "1_1") (pintype "passive"))
      (node (ref "U3") (pin "8") (pinfunction "RS_8") (pintype "bidirectional"))
    )
    (net (code "41") (name "Net-(U3-RXD)") (class "Default")
      (node (ref "R53") (pin "1") (pinfunction "1_1") (pintype "passive"))
      (node (ref "U3") (pin "4") (pinfunction "RXD_4") (pintype "bidirectional"))
    )
    (net (code "42") (name "Net-(U3-TXD)") (class "Default")
      (node (ref "R54") (pin "1") (pinfunction "1_1") (pintype "passive"))
      (node (ref "U3") (pin "1") (pinfunction "TXD_1") (pintype "bidirectional"))
    )
    (net (code "43") (name "OC_ADJ") (class "Default")
      (node (ref "R10") (pin "1") (pinfunction "1_1") (pintype "passive"))
      (node (ref "U1") (pin "14") (pinfunction "OC_ADJ_14") (pintype "passive"))
    )
    (net (code "44") (name "OUT_A") (class "Default")
      (node (ref "C1") (pin "1") (pinfunction "1_1") (pintype "passive"))
      (node (ref "R12") (pin "2") (pinfunction "2_2") (pintype "passive"))
      (node (ref "R3") (pin "2") (pinfunction "2_2") (pintype "passive"))
      (node (ref "U1") (pin "28") (pinfunction "OUT_A_28") (pintype "passive"))
    )
    (net (code "45") (name "OUT_A_W") (class "Default")
      (node (ref "R13") (pin "2") (pinfunction "2_2") (pintype "passive"))
      (node (ref "R3") (pin "1") (pinfunction "1_1") (pintype "passive"))
      (node (ref "X4") (pin "PIN1") (pinfunction "S_PIN1") (pintype "passive"))
    )
    (net (code "46") (name "OUT_B") (class "Default")
      (node (ref "C2") (pin "1") (pinfunction "1_1") (pintype "passive"))
      (node (ref "U1") (pin "31") (pinfunction "OUT_B_31") (pintype "passive"))
      (node (ref "X5") (pin "PIN1") (pinfunction "S_PIN1") (pintype "passive"))
    )
    (net (code "47") (name "OUT_C") (class "Default")
      (node (ref "C3") (pin "1") (pinfunction "1_1") (pintype "passive"))
      (node (ref "U1") (pin "36") (pinfunction "OUT_C_36") (pintype "passive"))
      (node (ref "X6") (pin "PIN1") (pinfunction "S_PIN1") (pintype "passive"))
    )
    (net (code "48") (name "OUT_D") (class "Default")
      (node (ref "C4") (pin "1") (pinfunction "1_1") (pintype "passive"))
      (node (ref "R15") (pin "2") (pinfunction "2_2") (pintype "passive"))
      (node (ref "R2") (pin "1") (pinfunction "1_1") (pintype "passive"))
      (node (ref "U1") (pin "39") (pinfunction "OUT_D_39") (pintype "passive"))
    )
    (net (code "49") (name "OUT_D_W") (class "Default")
      (node (ref "R14") (pin "2") (pinfunction "2_2") (pintype "passive"))
      (node (ref "R2") (pin "2") (pinfunction "2_2") (pintype "passive"))
      (node (ref "X7") (pin "PIN1") (pinfunction "S_PIN1") (pintype "passive"))
    )
    (net (code "50") (name "PWM_A") (class "Default")
      (node (ref "U1") (pin "17") (pinfunction "PWM_A_17") (pintype "passive"))
      (node (ref "U2") (pin "21") (pinfunction "PA5_21") (pintype "bidirectional"))
    )
    (net (code "51") (name "PWM_B") (class "Default")
      (node (ref "U1") (pin "15") (pinfunction "PWM_B_15") (pintype "passive"))
      (node (ref "U2") (pin "22") (pinfunction "PA6_22") (pintype "bidirectional"))
    )
    (net (code "52") (name "PWM_C") (class "Default")
      (node (ref "U1") (pin "7") (pinfunction "PWM_C_7") (pintype "passive"))
      (node (ref "U2") (pin "41") (pinfunction "PA8_41") (pintype "bidirectional"))
    )
    (net (code "53") (name "PWM_D") (class "Default")
      (node (ref "U1") (pin "5") (pinfunction "PWM_D_5") (pintype "passive"))
      (node (ref "U2") (pin "58") (pinfunction "PB6_58") (pintype "bidirectional"))
    )
    (net (code "54") (name "R-") (class "Default")
      (node (ref "X12") (pin "PIN1") (pinfunction "S_PIN1") (pintype "passive"))
    )
    (net (code "55") (name "RESET") (class "Default")
      (node (ref "D11") (pin "C") (pinfunction "C_C") (pintype "passive"))
    )
    (net (code "56") (name "RS") (class "Default")
      (node (ref "R50") (pin "2") (pinfunction "2_2") (pintype "passive"))
      (node (ref "U2") (pin "2") (pinfunction "PC13_2") (pintype "bidirectional"))
    )
    (net (code "57") (name "RXD") (class "Default")
      (node (ref "R53") (pin "2") (pinfunction "2_2") (pintype "passive"))
      (node (ref "U2") (pin "61") (pinfunction "PB8_61") (pintype "bidirectional"))
    )
    (net (code "58") (name "STO_IN") (class "Default")
      (node (ref "U2") (pin "10") (pinfunction "PC2_10") (pintype "bidirectional"))
      (node (ref "U7") (pin "1") (pinfunction "A_1") (pintype "bidirectional"))
      (node (ref "U8") (pin "1") (pinfunction "A_1") (pintype "bidirectional"))
      (node (ref "X10") (pin "8") (pinfunction "8_8") (pintype "bidirectional"))
    )
    (net (code "59") (name "SWCLK") (class "Default")
      (node (ref "U2") (pin "49") (pinfunction "PA14_49") (pintype "bidirectional"))
      (node (ref "X1") (pin "4") (pinfunction "4-SWCLK_4") (pintype "bidirectional"))
    )
    (net (code "60") (name "SWDIO") (class "Default")
      (node (ref "U2") (pin "46") (pinfunction "PA13_46") (pintype "bidirectional"))
      (node (ref "X1") (pin "2") (pinfunction "2-SWDIO_2") (pintype "bidirectional"))
    )
    (net (code "61") (name "SWO") (class "Default")
      (node (ref "U2") (pin "55") (pinfunction "PB3_55") (pintype "bidirectional"))
      (node (ref "X1") (pin "6") (pinfunction "6-SWO_6") (pintype "bidirectional"))
    )
    (net (code "62") (name "TXD") (class "Default")
      (node (ref "R54") (pin "2") (pinfunction "2_2") (pintype "passive"))
      (node (ref "U2") (pin "62") (pinfunction "PB9_62") (pintype "bidirectional"))
    )
    (net (code "63") (name "V+_SENSE") (class "Default")
      (node (ref "C41") (pin "1") (pinfunction "1_1") (pintype "passive"))
      (node (ref "D6") (pin "C") (pinfunction "C_C") (pintype "passive"))
      (node (ref "R38") (pin "2") (pinfunction "2_2") (pintype "passive"))
      (node (ref "R39") (pin "1") (pinfunction "1_1") (pintype "passive"))
      (node (ref "U2") (pin "8") (pinfunction "PC0_8") (pintype "bidirectional"))
    )
    (net (code "64") (name "VCAP1") (class "Default")
      (node (ref "C22") (pin "1") (pinfunction "1_1") (pintype "passive"))
      (node (ref "U2") (pin "31") (pinfunction "VCAP1_31") (pintype "bidirectional"))
    )
    (net (code "65") (name "VCAP2") (class "Default")
      (node (ref "C23") (pin "1") (pinfunction "1_1") (pintype "passive"))
      (node (ref "U2") (pin "47") (pinfunction "VCAP2_47") (pintype "bidirectional"))
    )
    (net (code "66") (name "VREG") (class "Default")
      (node (ref "C5") (pin "1") (pinfunction "1_1") (pintype "passive"))
      (node (ref "U1") (pin "11") (pinfunction "VREG_11") (pintype "passive"))
      (node (ref "U1") (pin "8") (pinfunction "M1_8") (pintype "passive"))
    )
    (net (code "67") (name "unconnected-(U1A-NC-Pad3)") (class "Default")
      (node (ref "U1") (pin "3") (pinfunction "NC_3") (pintype "passive"))
    )
    (net (code "68") (name "unconnected-(U1A-NC_2-Pad4)") (class "Default")
      (node (ref "U1") (pin "4") (pinfunction "NC_2_4") (pintype "passive"))
    )
    (net (code "69") (name "unconnected-(U1A-NC_3-Pad19)") (class "Default")
      (node (ref "U1") (pin "19") (pinfunction "NC_3_19") (pintype "passive"))
    )
    (net (code "70") (name "unconnected-(U1A-NC_4-Pad20)") (class "Default")
      (node (ref "U1") (pin "20") (pinfunction "NC_4_20") (pintype "passive"))
    )
    (net (code "71") (name "unconnected-(U1A-NC_5-Pad25)") (class "Default")
      (node (ref "U1") (pin "25") (pinfunction "NC_5_25") (pintype "passive"))
    )
    (net (code "72") (name "unconnected-(U1A-NC_6-Pad42)") (class "Default")
      (node (ref "U1") (pin "42") (pinfunction "NC_6_42") (pintype "passive"))
    )
    (net (code "73") (name "unconnected-(U2-PA4-Pad20)") (class "Default")
      (node (ref "U2") (pin "20") (pinfunction "PA4_20") (pintype "bidirectional"))
    )
    (net (code "74") (name "unconnected-(U2-PA7-Pad23)") (class "Default")
      (node (ref "U2") (pin "23") (pinfunction "PA7_23") (pintype "bidirectional"))
    )
    (net (code "75") (name "unconnected-(U2-PA9-Pad42)") (class "Default")
      (node (ref "U2") (pin "42") (pinfunction "PA9_42") (pintype "bidirectional"))
    )
    (net (code "76") (name "unconnected-(U2-PA11-Pad44)") (class "Default")
      (node (ref "U2") (pin "44") (pinfunction "PA11_44") (pintype "bidirectional"))
    )
    (net (code "77") (name "unconnected-(U2-PA12-Pad45)") (class "Default")
      (node (ref "U2") (pin "45") (pinfunction "PA12_45") (pintype "bidirectional"))
    )
    (net (code "78") (name "unconnected-(U2-PA15-Pad50)") (class "Default")
      (node (ref "U2") (pin "50") (pinfunction "PA15_50") (pintype "bidirectional"))
    )
    (net (code "79") (name "unconnected-(U2-PB0-Pad26)") (class "Default")
      (node (ref "U2") (pin "26") (pinfunction "PB0_26") (pintype "bidirectional"))
    )
    (net (code "80") (name "unconnected-(U2-PB4-Pad56)") (class "Default")
      (node (ref "U2") (pin "56") (pinfunction "PB4_56") (pintype "bidirectional"))
    )
    (net (code "81") (name "unconnected-(U2-PB5-Pad57)") (class "Default")
      (node (ref "U2") (pin "57") (pinfunction "PB5_57") (pintype "bidirectional"))
    )
    (net (code "82") (name "unconnected-(U2-PB7-Pad59)") (class "Default")
      (node (ref "U2") (pin "59") (pinfunction "PB7_59") (pintype "bidirectional"))
    )
    (net (code "83") (name "unconnected-(U2-PB10-Pad29)") (class "Default")
      (node (ref "U2") (pin "29") (pinfunction "PB10_29") (pintype "bidirectional"))
    )
    (net (code "84") (name "unconnected-(U2-PB11-Pad30)") (class "Default")
      (node (ref "U2") (pin "30") (pinfunction "PB11_30") (pintype "bidirectional"))
    )
    (net (code "85") (name "unconnected-(U2-PB12-Pad33)") (class "Default")
      (node (ref "U2") (pin "33") (pinfunction "PB12_33") (pintype "bidirectional"))
    )
    (net (code "86") (name "unconnected-(U2-PB13-Pad34)") (class "Default")
      (node (ref "U2") (pin "34") (pinfunction "PB13_34") (pintype "bidirectional"))
    )
    (net (code "87") (name "unconnected-(U2-PC1-Pad9)") (class "Default")
      (node (ref "U2") (pin "9") (pinfunction "PC1_9") (pintype "bidirectional"))
    )
    (net (code "88") (name "unconnected-(U2-PC3-Pad11)") (class "Default")
      (node (ref "U2") (pin "11") (pinfunction "PC3_11") (pintype "bidirectional"))
    )
    (net (code "89") (name "unconnected-(U2-PC6-Pad37)") (class "Default")
      (node (ref "U2") (pin "37") (pinfunction "PC6_37") (pintype "bidirectional"))
    )
    (net (code "90") (name "unconnected-(U2-PC9-Pad40)") (class "Default")
      (node (ref "U2") (pin "40") (pinfunction "PC9_40") (pintype "bidirectional"))
    )
    (net (code "91") (name "unconnected-(U2-PC15{slash}OSC32_OUT-Pad4)") (class "Default")
      (node (ref "U2") (pin "4") (pinfunction "PC15/OSC32_OUT_4") (pintype "bidirectional"))
    )
    (net (code "92") (name "~{FAULT}") (class "Default")
      (node (ref "U1") (pin "18") (pinfunction "~{FAULT}_18") (pintype "passive"))
      (node (ref "U2") (pin "39") (pinfunction "PC8_39") (pintype "bidirectional"))
    )
    (net (code "93") (name "~{OTW}") (class "Default")
      (node (ref "U1") (pin "21") (pinfunction "~{OTW}_21") (pintype "passive"))
      (node (ref "U2") (pin "38") (pinfunction "PC7_38") (pintype "bidirectional"))
    )
    (net (code "94") (name "~{RESET_AB}") (class "Default")
      (node (ref "U1") (pin "16") (pinfunction "~{RESET_AB}_16") (pintype "passive"))
      (node (ref "U7") (pin "4") (pinfunction "Y_4") (pintype "bidirectional"))
    )
    (net (code "95") (name "~{RESET_CD}") (class "Default")
      (node (ref "U1") (pin "6") (pinfunction "~{RESET_CD}_6") (pintype "passive"))
      (node (ref "U8") (pin "4") (pinfunction "Y_4") (pintype "bidirectional"))
    )
    (net (code "96") (name "~{RST_AB}") (class "Default")
      (node (ref "U2") (pin "36") (pinfunction "PB15_36") (pintype "bidirectional"))
      (node (ref "U7") (pin "2") (pinfunction "B_2") (pintype "bidirectional"))
    )
    (net (code "97") (name "~{RST_CD}") (class "Default")
      (node (ref "U2") (pin "35") (pinfunction "PB14_35") (pintype "bidirectional"))
      (node (ref "U8") (pin "2") (pinfunction "B_2") (pintype "bidirectional"))
    )
  )
)
